# RS485_RS232_Sheet.net
KiCad netlist of a schematic drawn in Altium Designer
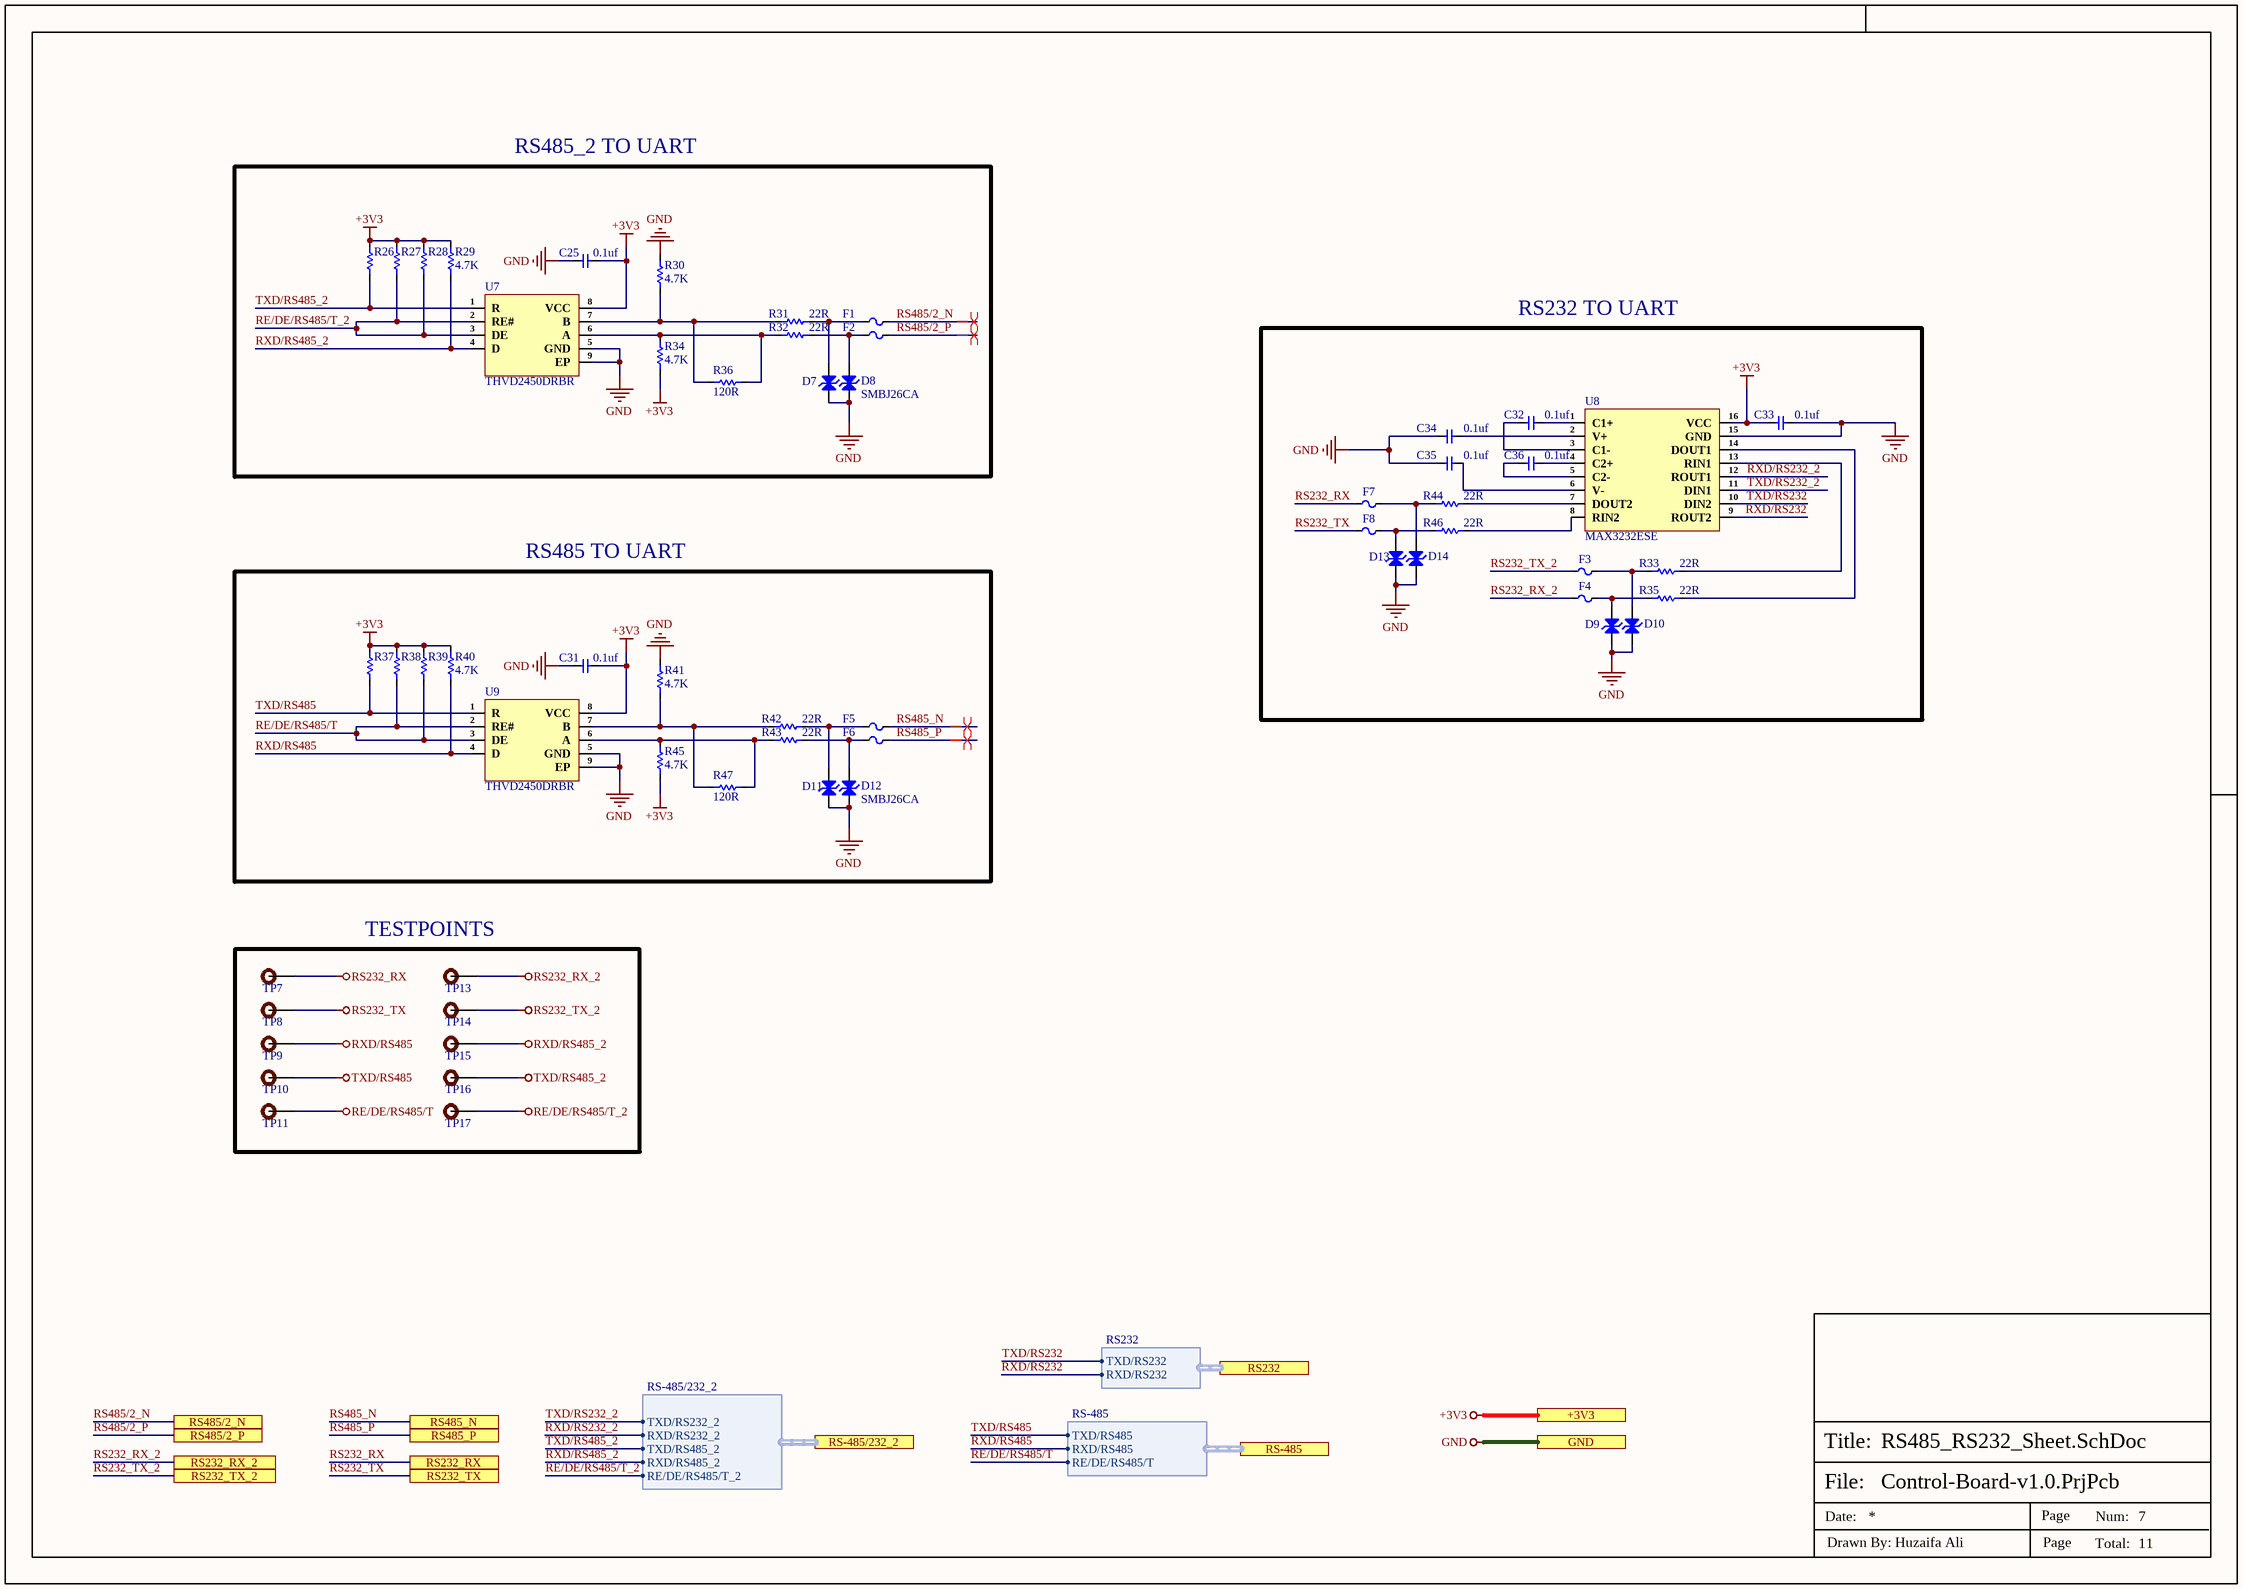
[diagram p0: RS485_RS232_Sheet.SchDoc]

(export (version "E")
  (design (tool "Eeschema 10.0.6"))
  (components
    (comp (ref "C25")
      (value "0.1uf")
      (footprint "Cap-0402")
      (description "CAP CER 0.1UF 100V X5R 0402")
      (fields
        (field (name "MANUFACTURER") "Murata")
        (field (name "MANUFACTURER PART NUMBER") "GRM155R62A104KE14D")
      )
      (libsource (lib "eSpark Libraries") (part "GRM155R62A104KE14D"))
    )
    (comp (ref "C31")
      (value "0.1uf")
      (footprint "Cap-0402")
      (description "CAP CER 0.1UF 100V X5R 0402")
      (fields
        (field (name "MANUFACTURER") "Murata")
        (field (name "MANUFACTURER PART NUMBER") "GRM155R62A104KE14D")
      )
      (libsource (lib "eSpark Libraries") (part "GRM155R62A104KE14D"))
    )
    (comp (ref "C32")
      (value "0.1uf")
      (footprint "Cap-0402")
      (description "CAP CER 0.1UF 100V X5R 0402")
      (fields
        (field (name "MANUFACTURER") "Murata")
        (field (name "MANUFACTURER PART NUMBER") "GRM155R62A104KE14D")
      )
      (libsource (lib "eSpark Libraries") (part "GRM155R62A104KE14D"))
    )
    (comp (ref "C33")
      (value "0.1uf")
      (footprint "Cap-0402")
      (description "CAP CER 0.1UF 100V X5R 0402")
      (fields
        (field (name "MANUFACTURER") "Murata")
        (field (name "MANUFACTURER PART NUMBER") "GRM155R62A104KE14D")
      )
      (libsource (lib "eSpark Libraries") (part "GRM155R62A104KE14D"))
    )
    (comp (ref "C34")
      (value "0.1uf")
      (footprint "Cap-0402")
      (description "CAP CER 0.1UF 100V X5R 0402")
      (fields
        (field (name "MANUFACTURER") "Murata")
        (field (name "MANUFACTURER PART NUMBER") "GRM155R62A104KE14D")
      )
      (libsource (lib "eSpark Libraries") (part "GRM155R62A104KE14D"))
    )
    (comp (ref "C35")
      (value "0.1uf")
      (footprint "Cap-0402")
      (description "CAP CER 0.1UF 100V X5R 0402")
      (fields
        (field (name "MANUFACTURER") "Murata")
        (field (name "MANUFACTURER PART NUMBER") "GRM155R62A104KE14D")
      )
      (libsource (lib "eSpark Libraries") (part "GRM155R62A104KE14D"))
    )
    (comp (ref "C36")
      (value "0.1uf")
      (footprint "Cap-0402")
      (description "CAP CER 0.1UF 100V X5R 0402")
      (fields
        (field (name "MANUFACTURER") "Murata")
        (field (name "MANUFACTURER PART NUMBER") "GRM155R62A104KE14D")
      )
      (libsource (lib "eSpark Libraries") (part "GRM155R62A104KE14D"))
    )
    (comp (ref "D7")
      (value "SMBJ26CA")
      (footprint "SMB Bi Directional")
      (description "SMB(DO-214AA) TVS ROHS")
      (fields (field (name "MANUFACTURER") "MSKSEMI") (field (name "LCSC PART NUMBER") "C5331111"))
      (libsource (lib "eSpark Libraries") (part "SMBJ26CA"))
    )
    (comp (ref "D8")
      (value "SMBJ26CA")
      (footprint "SMB Bi Directional")
      (description "SMB(DO-214AA) TVS ROHS")
      (fields (field (name "MANUFACTURER") "MSKSEMI") (field (name "LCSC PART NUMBER") "C5331111"))
      (libsource (lib "eSpark Libraries") (part "SMBJ26CA"))
    )
    (comp (ref "D9")
      (value "SMBJ26CA")
      (footprint "SMB Bi Directional")
      (description "SMB(DO-214AA) TVS ROHS")
      (fields (field (name "MANUFACTURER") "MSKSEMI") (field (name "LCSC PART NUMBER") "C5331111"))
      (libsource (lib "eSpark Libraries") (part "SMBJ26CA"))
    )
    (comp (ref "D10")
      (value "SMBJ26CA")
      (footprint "SMB Bi Directional")
      (description "SMB(DO-214AA) TVS ROHS")
      (fields (field (name "MANUFACTURER") "MSKSEMI") (field (name "LCSC PART NUMBER") "C5331111"))
      (libsource (lib "eSpark Libraries") (part "SMBJ26CA"))
    )
    (comp (ref "D11")
      (value "SMBJ26CA")
      (footprint "SMB Bi Directional")
      (description "SMB(DO-214AA) TVS ROHS")
      (fields (field (name "MANUFACTURER") "MSKSEMI") (field (name "LCSC PART NUMBER") "C5331111"))
      (libsource (lib "eSpark Libraries") (part "SMBJ26CA"))
    )
    (comp (ref "D12")
      (value "SMBJ26CA")
      (footprint "SMB Bi Directional")
      (description "SMB(DO-214AA) TVS ROHS")
      (fields (field (name "MANUFACTURER") "MSKSEMI") (field (name "LCSC PART NUMBER") "C5331111"))
      (libsource (lib "eSpark Libraries") (part "SMBJ26CA"))
    )
    (comp (ref "D13")
      (value "SMBJ26CA")
      (footprint "SMB Bi Directional")
      (description "SMB(DO-214AA) TVS ROHS")
      (fields (field (name "MANUFACTURER") "MSKSEMI") (field (name "LCSC PART NUMBER") "C5331111"))
      (libsource (lib "eSpark Libraries") (part "SMBJ26CA"))
    )
    (comp (ref "D14")
      (value "SMBJ26CA")
      (footprint "SMB Bi Directional")
      (description "SMB(DO-214AA) TVS ROHS")
      (fields (field (name "MANUFACTURER") "MSKSEMI") (field (name "LCSC PART NUMBER") "C5331111"))
      (libsource (lib "eSpark Libraries") (part "SMBJ26CA"))
    )
    (comp (ref "F1")
      (value "SMD0805P020TF")
      (footprint "Fuse-0805")
      (description "9V 200mA 100A 500mA 0805 Resettable Fuses ROHS")
      (fields (field (name "MANUFACTURER") "RUILON") (field (name "LCSC PART NUMBER") "C20976"))
      (libsource (lib "eSpark_centralized_Library(2022)") (part "SMD0805P020TF"))
    )
    (comp (ref "F2")
      (value "SMD0805P020TF")
      (footprint "Fuse-0805")
      (description "9V 200mA 100A 500mA 0805 Resettable Fuses ROHS")
      (fields (field (name "MANUFACTURER") "RUILON") (field (name "LCSC PART NUMBER") "C20976"))
      (libsource (lib "eSpark_centralized_Library(2022)") (part "SMD0805P020TF"))
    )
    (comp (ref "F3")
      (value "SMD0805P020TF")
      (footprint "Fuse-0805")
      (description "9V 200mA 100A 500mA 0805 Resettable Fuses ROHS")
      (fields (field (name "MANUFACTURER") "RUILON") (field (name "LCSC PART NUMBER") "C20976"))
      (libsource (lib "eSpark Libraries") (part "SMD0805P020TF"))
    )
    (comp (ref "F4")
      (value "SMD0805P020TF")
      (footprint "Fuse-0805")
      (description "9V 200mA 100A 500mA 0805 Resettable Fuses ROHS")
      (fields (field (name "MANUFACTURER") "RUILON") (field (name "LCSC PART NUMBER") "C20976"))
      (libsource (lib "eSpark Libraries") (part "SMD0805P020TF"))
    )
    (comp (ref "F5")
      (value "SMD0805P020TF")
      (footprint "Fuse-0805")
      (description "9V 200mA 100A 500mA 0805 Resettable Fuses ROHS")
      (fields (field (name "MANUFACTURER") "RUILON") (field (name "LCSC PART NUMBER") "C20976"))
      (libsource (lib "eSpark_centralized_Library(2022)") (part "SMD0805P020TF"))
    )
    (comp (ref "F6")
      (value "SMD0805P020TF")
      (footprint "Fuse-0805")
      (description "9V 200mA 100A 500mA 0805 Resettable Fuses ROHS")
      (fields (field (name "MANUFACTURER") "RUILON") (field (name "LCSC PART NUMBER") "C20976"))
      (libsource (lib "eSpark_centralized_Library(2022)") (part "SMD0805P020TF"))
    )
    (comp (ref "F7")
      (value "SMD0805P020TF")
      (footprint "Fuse-0805")
      (description "9V 200mA 100A 500mA 0805 Resettable Fuses ROHS")
      (fields (field (name "MANUFACTURER") "RUILON") (field (name "LCSC PART NUMBER") "C20976"))
      (libsource (lib "eSpark Libraries") (part "SMD0805P020TF"))
    )
    (comp (ref "F8")
      (value "SMD0805P020TF")
      (footprint "Fuse-0805")
      (description "9V 200mA 100A 500mA 0805 Resettable Fuses ROHS")
      (fields (field (name "MANUFACTURER") "RUILON") (field (name "LCSC PART NUMBER") "C20976"))
      (libsource (lib "eSpark Libraries") (part "SMD0805P020TF"))
    )
    (comp (ref "R26")
      (value "4.7K")
      (footprint "Res-0402")
      (description "RES 4.7K OHM 1% 1/16W 0402")
      (fields
        (field (name "MANUFACTURER") "Yageo")
        (field (name "MANUFACTURER PART NUMBER") "RC0402FR-074K7L")
      )
      (libsource (lib "eSpark Libraries") (part "RC0402FR-074K7L"))
    )
    (comp (ref "R27")
      (value "4.7K")
      (footprint "Res-0402")
      (description "RES 4.7K OHM 1% 1/16W 0402")
      (fields
        (field (name "MANUFACTURER") "Yageo")
        (field (name "MANUFACTURER PART NUMBER") "RC0402FR-074K7L")
      )
      (libsource (lib "eSpark Libraries") (part "RC0402FR-074K7L"))
    )
    (comp (ref "R28")
      (value "4.7K")
      (footprint "Res-0402")
      (description "RES 4.7K OHM 1% 1/16W 0402")
      (fields
        (field (name "MANUFACTURER") "Yageo")
        (field (name "MANUFACTURER PART NUMBER") "RC0402FR-074K7L")
      )
      (libsource (lib "eSpark Libraries") (part "RC0402FR-074K7L"))
    )
    (comp (ref "R29")
      (value "4.7K")
      (footprint "Res-0402")
      (description "RES 4.7K OHM 1% 1/16W 0402")
      (fields
        (field (name "MANUFACTURER") "Yageo")
        (field (name "MANUFACTURER PART NUMBER") "RC0402FR-074K7L")
      )
      (libsource (lib "eSpark Libraries") (part "RC0402FR-074K7L"))
    )
    (comp (ref "R30")
      (value "4.7K")
      (footprint "Res-0402")
      (description "RES 4.7K OHM 1% 1/16W 0402")
      (fields
        (field (name "MANUFACTURER") "Yageo")
        (field (name "MANUFACTURER PART NUMBER") "RC0402FR-074K7L")
      )
      (libsource (lib "eSpark Libraries") (part "RC0402FR-074K7L"))
    )
    (comp (ref "R31")
      (value "22R")
      (footprint "Res-0201")
      (description "RES 22 OHM 1% 1/20W 0201")
      (fields
        (field (name "MANUFACTURER") "Yageo")
        (field (name "MANUFACTURER PART NUMBER") "RC0201FR-0722RL")
      )
      (libsource (lib "eSpark Libraries") (part "RC0201FR-0722RL"))
    )
    (comp (ref "R32")
      (value "22R")
      (footprint "Res-0201")
      (description "RES 22 OHM 1% 1/20W 0201")
      (fields
        (field (name "MANUFACTURER") "Yageo")
        (field (name "MANUFACTURER PART NUMBER") "RC0201FR-0722RL")
      )
      (libsource (lib "eSpark Libraries") (part "RC0201FR-0722RL"))
    )
    (comp (ref "R33")
      (value "22R")
      (footprint "Res-0201")
      (description "RES 22 OHM 1% 1/20W 0201")
      (fields
        (field (name "MANUFACTURER") "Yageo")
        (field (name "MANUFACTURER PART NUMBER") "RC0201FR-0722RL")
      )
      (libsource (lib "eSpark Libraries") (part "RC0201FR-0722RL"))
    )
    (comp (ref "R34")
      (value "4.7K")
      (footprint "Res-0402")
      (description "RES 4.7K OHM 1% 1/16W 0402")
      (fields
        (field (name "MANUFACTURER") "Yageo")
        (field (name "MANUFACTURER PART NUMBER") "RC0402FR-074K7L")
      )
      (libsource (lib "eSpark Libraries") (part "RC0402FR-074K7L"))
    )
    (comp (ref "R35")
      (value "22R")
      (footprint "Res-0201")
      (description "RES 22 OHM 1% 1/20W 0201")
      (fields
        (field (name "MANUFACTURER") "Yageo")
        (field (name "MANUFACTURER PART NUMBER") "RC0201FR-0722RL")
      )
      (libsource (lib "eSpark Libraries") (part "RC0201FR-0722RL"))
    )
    (comp (ref "R36")
      (value "120R")
      (footprint "Res-0603")
      (description "RES 120 OHM 5% 1/10W 0603")
      (fields
        (field (name "MANUFACTURER") "Yageo")
        (field (name "MANUFACTURER PART NUMBER") "RC0603JR-07120RL")
      )
      (libsource (lib "eSpark Libraries") (part "RC0603JR-07120RL"))
    )
    (comp (ref "R37")
      (value "4.7K")
      (footprint "Res-0402")
      (description "RES 4.7K OHM 1% 1/16W 0402")
      (fields
        (field (name "MANUFACTURER") "Yageo")
        (field (name "MANUFACTURER PART NUMBER") "RC0402FR-074K7L")
      )
      (libsource (lib "eSpark Libraries") (part "RC0402FR-074K7L"))
    )
    (comp (ref "R38")
      (value "4.7K")
      (footprint "Res-0402")
      (description "RES 4.7K OHM 1% 1/16W 0402")
      (fields
        (field (name "MANUFACTURER") "Yageo")
        (field (name "MANUFACTURER PART NUMBER") "RC0402FR-074K7L")
      )
      (libsource (lib "eSpark Libraries") (part "RC0402FR-074K7L"))
    )
    (comp (ref "R39")
      (value "4.7K")
      (footprint "Res-0402")
      (description "RES 4.7K OHM 1% 1/16W 0402")
      (fields
        (field (name "MANUFACTURER") "Yageo")
        (field (name "MANUFACTURER PART NUMBER") "RC0402FR-074K7L")
      )
      (libsource (lib "eSpark Libraries") (part "RC0402FR-074K7L"))
    )
    (comp (ref "R40")
      (value "4.7K")
      (footprint "Res-0402")
      (description "RES 4.7K OHM 1% 1/16W 0402")
      (fields
        (field (name "MANUFACTURER") "Yageo")
        (field (name "MANUFACTURER PART NUMBER") "RC0402FR-074K7L")
      )
      (libsource (lib "eSpark Libraries") (part "RC0402FR-074K7L"))
    )
    (comp (ref "R41")
      (value "4.7K")
      (footprint "Res-0402")
      (description "RES 4.7K OHM 1% 1/16W 0402")
      (fields
        (field (name "MANUFACTURER") "Yageo")
        (field (name "MANUFACTURER PART NUMBER") "RC0402FR-074K7L")
      )
      (libsource (lib "eSpark Libraries") (part "RC0402FR-074K7L"))
    )
    (comp (ref "R42")
      (value "22R")
      (footprint "Res-0201")
      (description "RES 22 OHM 1% 1/20W 0201")
      (fields
        (field (name "MANUFACTURER") "Yageo")
        (field (name "MANUFACTURER PART NUMBER") "RC0201FR-0722RL")
      )
      (libsource (lib "eSpark Libraries") (part "RC0201FR-0722RL"))
    )
    (comp (ref "R43")
      (value "22R")
      (footprint "Res-0201")
      (description "RES 22 OHM 1% 1/20W 0201")
      (fields
        (field (name "MANUFACTURER") "Yageo")
        (field (name "MANUFACTURER PART NUMBER") "RC0201FR-0722RL")
      )
      (libsource (lib "eSpark Libraries") (part "RC0201FR-0722RL"))
    )
    (comp (ref "R44")
      (value "22R")
      (footprint "Res-0201")
      (description "RES 22 OHM 1% 1/20W 0201")
      (fields
        (field (name "MANUFACTURER") "Yageo")
        (field (name "MANUFACTURER PART NUMBER") "RC0201FR-0722RL")
      )
      (libsource (lib "eSpark Libraries") (part "RC0201FR-0722RL"))
    )
    (comp (ref "R45")
      (value "4.7K")
      (footprint "Res-0402")
      (description "RES 4.7K OHM 1% 1/16W 0402")
      (fields
        (field (name "MANUFACTURER") "Yageo")
        (field (name "MANUFACTURER PART NUMBER") "RC0402FR-074K7L")
      )
      (libsource (lib "eSpark Libraries") (part "RC0402FR-074K7L"))
    )
    (comp (ref "R46")
      (value "22R")
      (footprint "Res-0201")
      (description "RES 22 OHM 1% 1/20W 0201")
      (fields
        (field (name "MANUFACTURER") "Yageo")
        (field (name "MANUFACTURER PART NUMBER") "RC0201FR-0722RL")
      )
      (libsource (lib "eSpark Libraries") (part "RC0201FR-0722RL"))
    )
    (comp (ref "R47")
      (value "120R")
      (footprint "Res-0603")
      (description "RES 120 OHM 5% 1/10W 0603")
      (fields
        (field (name "MANUFACTURER") "Yageo")
        (field (name "MANUFACTURER PART NUMBER") "RC0603JR-07120RL")
      )
      (libsource (lib "eSpark Libraries") (part "RC0603JR-07120RL"))
    )
    (comp (ref "TP7")
      (value "TEST POINT")
      (footprint "Test-point")
      (description "Test Point ON")
      (libsource (lib "eSpark Libraries") (part "TEST POINT"))
    )
    (comp (ref "TP8")
      (value "TEST POINT")
      (footprint "Test-point")
      (description "Test Point ON")
      (libsource (lib "eSpark Libraries") (part "TEST POINT"))
    )
    (comp (ref "TP9")
      (value "TEST POINT")
      (footprint "Test-point")
      (description "Test Point ON")
      (libsource (lib "eSpark Libraries") (part "TEST POINT"))
    )
    (comp (ref "TP10")
      (value "TEST POINT")
      (footprint "Test-point")
      (description "Test Point ON")
      (libsource (lib "eSpark Libraries") (part "TEST POINT"))
    )
    (comp (ref "TP11")
      (value "TEST POINT")
      (footprint "Test-point")
      (description "Test Point ON")
      (libsource (lib "eSpark Libraries") (part "TEST POINT"))
    )
    (comp (ref "TP13")
      (value "TEST POINT")
      (footprint "Test-point")
      (description "Test Point ON")
      (libsource (lib "eSpark Libraries") (part "TEST POINT"))
    )
    (comp (ref "TP14")
      (value "TEST POINT")
      (footprint "Test-point")
      (description "Test Point ON")
      (libsource (lib "eSpark Libraries") (part "TEST POINT"))
    )
    (comp (ref "TP15")
      (value "TEST POINT")
      (footprint "Test-point")
      (description "Test Point ON")
      (libsource (lib "eSpark Libraries") (part "TEST POINT"))
    )
    (comp (ref "TP16")
      (value "TEST POINT")
      (footprint "Test-point")
      (description "Test Point ON")
      (libsource (lib "eSpark Libraries") (part "TEST POINT"))
    )
    (comp (ref "TP17")
      (value "TEST POINT")
      (footprint "Test-point")
      (description "Test Point ON")
      (libsource (lib "eSpark Libraries") (part "TEST POINT"))
    )
    (comp (ref "U7")
      (value "THVD2450DRBR")
      (footprint "SON-8-EP(3x3)")
      (description "IC TRANSCEIVER HALF 1/1 8SON")
      (fields (field (name "MANUFACTURER") "Texas Instruments") (field (name "LCSC PART NUMBER") "C2878080"))
      (libsource (lib "eSpark Libraries") (part "THVD2450DRBR"))
    )
    (comp (ref "U8")
      (value "MAX3232ESE")
      (footprint "SOP-16")
      (description "250Kbps transceiver 2/2 SOP-16 RS232 ICs ROHS")
      (fields (field (name "MANUFACTURER") "UMW") (field (name "LCSC PART NUMBER") "C2904738"))
      (libsource (lib "eSpark Libraries") (part "MAX3232ESE"))
    )
    (comp (ref "U9")
      (value "THVD2450DRBR")
      (footprint "SON-8-EP(3x3)")
      (description "IC TRANSCEIVER HALF 1/1 8SON")
      (fields (field (name "MANUFACTURER") "Texas Instruments") (field (name "LCSC PART NUMBER") "C2878080"))
      (libsource (lib "eSpark Libraries") (part "THVD2450DRBR"))
    )
  )
  (nets
    (net (code "4") (name "+3V3") (class "Default")
      (node (ref "C25") (pin "2") (pinfunction "2_2") (pintype "passive"))
      (node (ref "C31") (pin "2") (pinfunction "2_2") (pintype "passive"))
      (node (ref "C33") (pin "2") (pinfunction "2_2") (pintype "passive"))
      (node (ref "R26") (pin "2") (pinfunction "2_2") (pintype "passive"))
      (node (ref "R27") (pin "2") (pinfunction "2_2") (pintype "passive"))
      (node (ref "R28") (pin "2") (pinfunction "2_2") (pintype "passive"))
      (node (ref "R29") (pin "2") (pinfunction "2_2") (pintype "passive"))
      (node (ref "R34") (pin "1") (pinfunction "1_1") (pintype "passive"))
      (node (ref "R37") (pin "2") (pinfunction "2_2") (pintype "passive"))
      (node (ref "R38") (pin "2") (pinfunction "2_2") (pintype "passive"))
      (node (ref "R39") (pin "2") (pinfunction "2_2") (pintype "passive"))
      (node (ref "R40") (pin "2") (pinfunction "2_2") (pintype "passive"))
      (node (ref "R45") (pin "1") (pinfunction "1_1") (pintype "passive"))
      (node (ref "U7") (pin "8") (pinfunction "VCC_8") (pintype "passive"))
      (node (ref "U8") (pin "16") (pinfunction "VCC_16") (pintype "passive"))
      (node (ref "U9") (pin "8") (pinfunction "VCC_8") (pintype "passive"))
    )
    (net (code "5") (name "/RS485_N") (class "Default")
      (node (ref "F5") (pin "2") (pinfunction "2_2") (pintype "passive"))
    )
    (net (code "6") (name "/RS485_P") (class "Default")
      (node (ref "F6") (pin "2") (pinfunction "2_2") (pintype "passive"))
    )
    (net (code "7") (name "/RS485{slash}2_N") (class "Default")
      (node (ref "F1") (pin "2") (pinfunction "2_2") (pintype "passive"))
    )
    (net (code "8") (name "/RS485{slash}2_P") (class "Default")
      (node (ref "F2") (pin "2") (pinfunction "2_2") (pintype "passive"))
    )
    (net (code "9") (name "/RXD{slash}RS232") (class "Default")
      (node (ref "U8") (pin "9") (pinfunction "ROUT2_9") (pintype "passive"))
    )
    (net (code "10") (name "/RXD{slash}RS232_2") (class "Default")
      (node (ref "U8") (pin "12") (pinfunction "ROUT1_12") (pintype "passive"))
    )
    (net (code "11") (name "/TXD{slash}RS232") (class "Default")
      (node (ref "U8") (pin "10") (pinfunction "DIN2_10") (pintype "passive"))
    )
    (net (code "12") (name "/TXD{slash}RS232_2") (class "Default")
      (node (ref "U8") (pin "11") (pinfunction "DIN1_11") (pintype "passive"))
    )
    (net (code "16") (name "GND") (class "Default")
      (node (ref "C25") (pin "1") (pinfunction "1_1") (pintype "passive"))
      (node (ref "C31") (pin "1") (pinfunction "1_1") (pintype "passive"))
      (node (ref "C33") (pin "1") (pinfunction "1_1") (pintype "passive"))
      (node (ref "C34") (pin "1") (pinfunction "1_1") (pintype "passive"))
      (node (ref "C35") (pin "1") (pinfunction "1_1") (pintype "passive"))
      (node (ref "D10") (pin "1") (pinfunction "A_1") (pintype "passive"))
      (node (ref "D11") (pin "1") (pinfunction "A_1") (pintype "passive"))
      (node (ref "D12") (pin "1") (pinfunction "A_1") (pintype "passive"))
      (node (ref "D13") (pin "1") (pinfunction "A_1") (pintype "passive"))
      (node (ref "D14") (pin "1") (pinfunction "A_1") (pintype "passive"))
      (node (ref "D7") (pin "1") (pinfunction "A_1") (pintype "passive"))
      (node (ref "D8") (pin "1") (pinfunction "A_1") (pintype "passive"))
      (node (ref "D9") (pin "1") (pinfunction "A_1") (pintype "passive"))
      (node (ref "R30") (pin "2") (pinfunction "2_2") (pintype "passive"))
      (node (ref "R41") (pin "2") (pinfunction "2_2") (pintype "passive"))
      (node (ref "U7") (pin "5") (pinfunction "GND_5") (pintype "passive"))
      (node (ref "U7") (pin "9") (pinfunction "EP_9") (pintype "passive"))
      (node (ref "U8") (pin "15") (pinfunction "GND_15") (pintype "passive"))
      (node (ref "U9") (pin "5") (pinfunction "GND_5") (pintype "passive"))
      (node (ref "U9") (pin "9") (pinfunction "EP_9") (pintype "passive"))
    )
    (net (code "17") (name "Net-(D7-K)") (class "Default")
      (node (ref "D7") (pin "2") (pinfunction "K_2") (pintype "passive"))
      (node (ref "F1") (pin "1") (pinfunction "1_1") (pintype "passive"))
      (node (ref "R31") (pin "2") (pinfunction "2_2") (pintype "passive"))
    )
    (net (code "18") (name "Net-(D8-K)") (class "Default")
      (node (ref "D8") (pin "2") (pinfunction "K_2") (pintype "passive"))
      (node (ref "F2") (pin "1") (pinfunction "1_1") (pintype "passive"))
      (node (ref "R32") (pin "2") (pinfunction "2_2") (pintype "passive"))
    )
    (net (code "19") (name "Net-(D9-K)") (class "Default")
      (node (ref "D9") (pin "2") (pinfunction "K_2") (pintype "passive"))
      (node (ref "F4") (pin "2") (pinfunction "2_2") (pintype "passive"))
      (node (ref "R35") (pin "1") (pinfunction "1_1") (pintype "passive"))
    )
    (net (code "20") (name "Net-(D10-K)") (class "Default")
      (node (ref "D10") (pin "2") (pinfunction "K_2") (pintype "passive"))
      (node (ref "F3") (pin "2") (pinfunction "2_2") (pintype "passive"))
      (node (ref "R33") (pin "1") (pinfunction "1_1") (pintype "passive"))
    )
    (net (code "21") (name "Net-(D11-K)") (class "Default")
      (node (ref "D11") (pin "2") (pinfunction "K_2") (pintype "passive"))
      (node (ref "F5") (pin "1") (pinfunction "1_1") (pintype "passive"))
      (node (ref "R42") (pin "2") (pinfunction "2_2") (pintype "passive"))
    )
    (net (code "22") (name "Net-(D12-K)") (class "Default")
      (node (ref "D12") (pin "2") (pinfunction "K_2") (pintype "passive"))
      (node (ref "F6") (pin "1") (pinfunction "1_1") (pintype "passive"))
      (node (ref "R43") (pin "2") (pinfunction "2_2") (pintype "passive"))
    )
    (net (code "23") (name "Net-(D13-K)") (class "Default")
      (node (ref "D13") (pin "2") (pinfunction "K_2") (pintype "passive"))
      (node (ref "F8") (pin "2") (pinfunction "2_2") (pintype "passive"))
      (node (ref "R46") (pin "1") (pinfunction "1_1") (pintype "passive"))
    )
    (net (code "24") (name "Net-(D14-K)") (class "Default")
      (node (ref "D14") (pin "2") (pinfunction "K_2") (pintype "passive"))
      (node (ref "F7") (pin "2") (pinfunction "2_2") (pintype "passive"))
      (node (ref "R44") (pin "1") (pinfunction "1_1") (pintype "passive"))
    )
    (net (code "25") (name "Net-(U7-A)") (class "Default")
      (node (ref "R32") (pin "1") (pinfunction "1_1") (pintype "passive"))
      (node (ref "R34") (pin "2") (pinfunction "2_2") (pintype "passive"))
      (node (ref "R36") (pin "2") (pinfunction "2_2") (pintype "passive"))
      (node (ref "U7") (pin "6") (pinfunction "A_6") (pintype "passive"))
    )
    (net (code "26") (name "Net-(U7-B)") (class "Default")
      (node (ref "R30") (pin "1") (pinfunction "1_1") (pintype "passive"))
      (node (ref "R31") (pin "1") (pinfunction "1_1") (pintype "passive"))
      (node (ref "R36") (pin "1") (pinfunction "1_1") (pintype "passive"))
      (node (ref "U7") (pin "7") (pinfunction "B_7") (pintype "passive"))
    )
    (net (code "27") (name "Net-(U8-C1+)") (class "Default")
      (node (ref "C32") (pin "1") (pinfunction "1_1") (pintype "passive"))
      (node (ref "U8") (pin "1") (pinfunction "C1+_1") (pintype "passive"))
    )
    (net (code "28") (name "Net-(U8-C1-)") (class "Default")
      (node (ref "C32") (pin "2") (pinfunction "2_2") (pintype "passive"))
      (node (ref "U8") (pin "3") (pinfunction "C1-_3") (pintype "passive"))
    )
    (net (code "29") (name "Net-(U8-C2+)") (class "Default")
      (node (ref "C36") (pin "1") (pinfunction "1_1") (pintype "passive"))
      (node (ref "U8") (pin "4") (pinfunction "C2+_4") (pintype "passive"))
    )
    (net (code "30") (name "Net-(U8-C2-)") (class "Default")
      (node (ref "C36") (pin "2") (pinfunction "2_2") (pintype "passive"))
      (node (ref "U8") (pin "5") (pinfunction "C2-_5") (pintype "passive"))
    )
    (net (code "31") (name "Net-(U8-DOUT1)") (class "Default")
      (node (ref "R35") (pin "2") (pinfunction "2_2") (pintype "passive"))
      (node (ref "U8") (pin "14") (pinfunction "DOUT1_14") (pintype "passive"))
    )
    (net (code "32") (name "Net-(U8-DOUT2)") (class "Default")
      (node (ref "R44") (pin "2") (pinfunction "2_2") (pintype "passive"))
      (node (ref "U8") (pin "7") (pinfunction "DOUT2_7") (pintype "passive"))
    )
    (net (code "33") (name "Net-(U8-RIN1)") (class "Default")
      (node (ref "R33") (pin "2") (pinfunction "2_2") (pintype "passive"))
      (node (ref "U8") (pin "13") (pinfunction "RIN1_13") (pintype "passive"))
    )
    (net (code "34") (name "Net-(U8-RIN2)") (class "Default")
      (node (ref "R46") (pin "2") (pinfunction "2_2") (pintype "passive"))
      (node (ref "U8") (pin "8") (pinfunction "RIN2_8") (pintype "passive"))
    )
    (net (code "35") (name "Net-(U8-V+)") (class "Default")
      (node (ref "C34") (pin "2") (pinfunction "2_2") (pintype "passive"))
      (node (ref "U8") (pin "2") (pinfunction "V+_2") (pintype "passive"))
    )
    (net (code "36") (name "Net-(U8-V-)") (class "Default")
      (node (ref "C35") (pin "2") (pinfunction "2_2") (pintype "passive"))
      (node (ref "U8") (pin "6") (pinfunction "V-_6") (pintype "passive"))
    )
    (net (code "37") (name "Net-(U9-A)") (class "Default")
      (node (ref "R43") (pin "1") (pinfunction "1_1") (pintype "passive"))
      (node (ref "R45") (pin "2") (pinfunction "2_2") (pintype "passive"))
      (node (ref "R47") (pin "2") (pinfunction "2_2") (pintype "passive"))
      (node (ref "U9") (pin "6") (pinfunction "A_6") (pintype "passive"))
    )
    (net (code "38") (name "Net-(U9-B)") (class "Default")
      (node (ref "R41") (pin "1") (pinfunction "1_1") (pintype "passive"))
      (node (ref "R42") (pin "1") (pinfunction "1_1") (pintype "passive"))
      (node (ref "R47") (pin "1") (pinfunction "1_1") (pintype "passive"))
      (node (ref "U9") (pin "7") (pinfunction "B_7") (pintype "passive"))
    )
    (net (code "39") (name "RE{slash}DE{slash}RS485{slash}T") (class "Default")
      (node (ref "R38") (pin "1") (pinfunction "1_1") (pintype "passive"))
      (node (ref "R39") (pin "1") (pinfunction "1_1") (pintype "passive"))
      (node (ref "TP11") (pin "1") (pinfunction "1_1") (pintype "passive"))
      (node (ref "U9") (pin "2") (pinfunction "RE#_2") (pintype "passive"))
      (node (ref "U9") (pin "3") (pinfunction "DE_3") (pintype "passive"))
    )
    (net (code "40") (name "RE{slash}DE{slash}RS485{slash}T_2") (class "Default")
      (node (ref "R27") (pin "1") (pinfunction "1_1") (pintype "passive"))
      (node (ref "R28") (pin "1") (pinfunction "1_1") (pintype "passive"))
      (node (ref "TP17") (pin "1") (pinfunction "1_1") (pintype "passive"))
      (node (ref "U7") (pin "2") (pinfunction "RE#_2") (pintype "passive"))
      (node (ref "U7") (pin "3") (pinfunction "DE_3") (pintype "passive"))
    )
    (net (code "41") (name "RS232_RX") (class "Default")
      (node (ref "F7") (pin "1") (pinfunction "1_1") (pintype "passive"))
      (node (ref "TP7") (pin "1") (pinfunction "1_1") (pintype "passive"))
    )
    (net (code "42") (name "RS232_RX_2") (class "Default")
      (node (ref "F4") (pin "1") (pinfunction "1_1") (pintype "passive"))
      (node (ref "TP13") (pin "1") (pinfunction "1_1") (pintype "passive"))
    )
    (net (code "43") (name "RS232_TX") (class "Default")
      (node (ref "F8") (pin "1") (pinfunction "1_1") (pintype "passive"))
      (node (ref "TP8") (pin "1") (pinfunction "1_1") (pintype "passive"))
    )
    (net (code "44") (name "RS232_TX_2") (class "Default")
      (node (ref "F3") (pin "1") (pinfunction "1_1") (pintype "passive"))
      (node (ref "TP14") (pin "1") (pinfunction "1_1") (pintype "passive"))
    )
    (net (code "45") (name "RXD{slash}RS485") (class "Default")
      (node (ref "R40") (pin "1") (pinfunction "1_1") (pintype "passive"))
      (node (ref "TP9") (pin "1") (pinfunction "1_1") (pintype "passive"))
      (node (ref "U9") (pin "4") (pinfunction "D_4") (pintype "passive"))
    )
    (net (code "46") (name "RXD{slash}RS485_2") (class "Default")
      (node (ref "R29") (pin "1") (pinfunction "1_1") (pintype "passive"))
      (node (ref "TP15") (pin "1") (pinfunction "1_1") (pintype "passive"))
      (node (ref "U7") (pin "4") (pinfunction "D_4") (pintype "passive"))
    )
    (net (code "47") (name "TXD{slash}RS485") (class "Default")
      (node (ref "R37") (pin "1") (pinfunction "1_1") (pintype "passive"))
      (node (ref "TP10") (pin "1") (pinfunction "1_1") (pintype "passive"))
      (node (ref "U9") (pin "1") (pinfunction "R_1") (pintype "passive"))
    )
    (net (code "48") (name "TXD{slash}RS485_2") (class "Default")
      (node (ref "R26") (pin "1") (pinfunction "1_1") (pintype "passive"))
      (node (ref "TP16") (pin "1") (pinfunction "1_1") (pintype "passive"))
      (node (ref "U7") (pin "1") (pinfunction "R_1") (pintype "passive"))
    )
  )
)
